# pureVCO.net
KiCad netlist of a schematic drawn in EAGLE
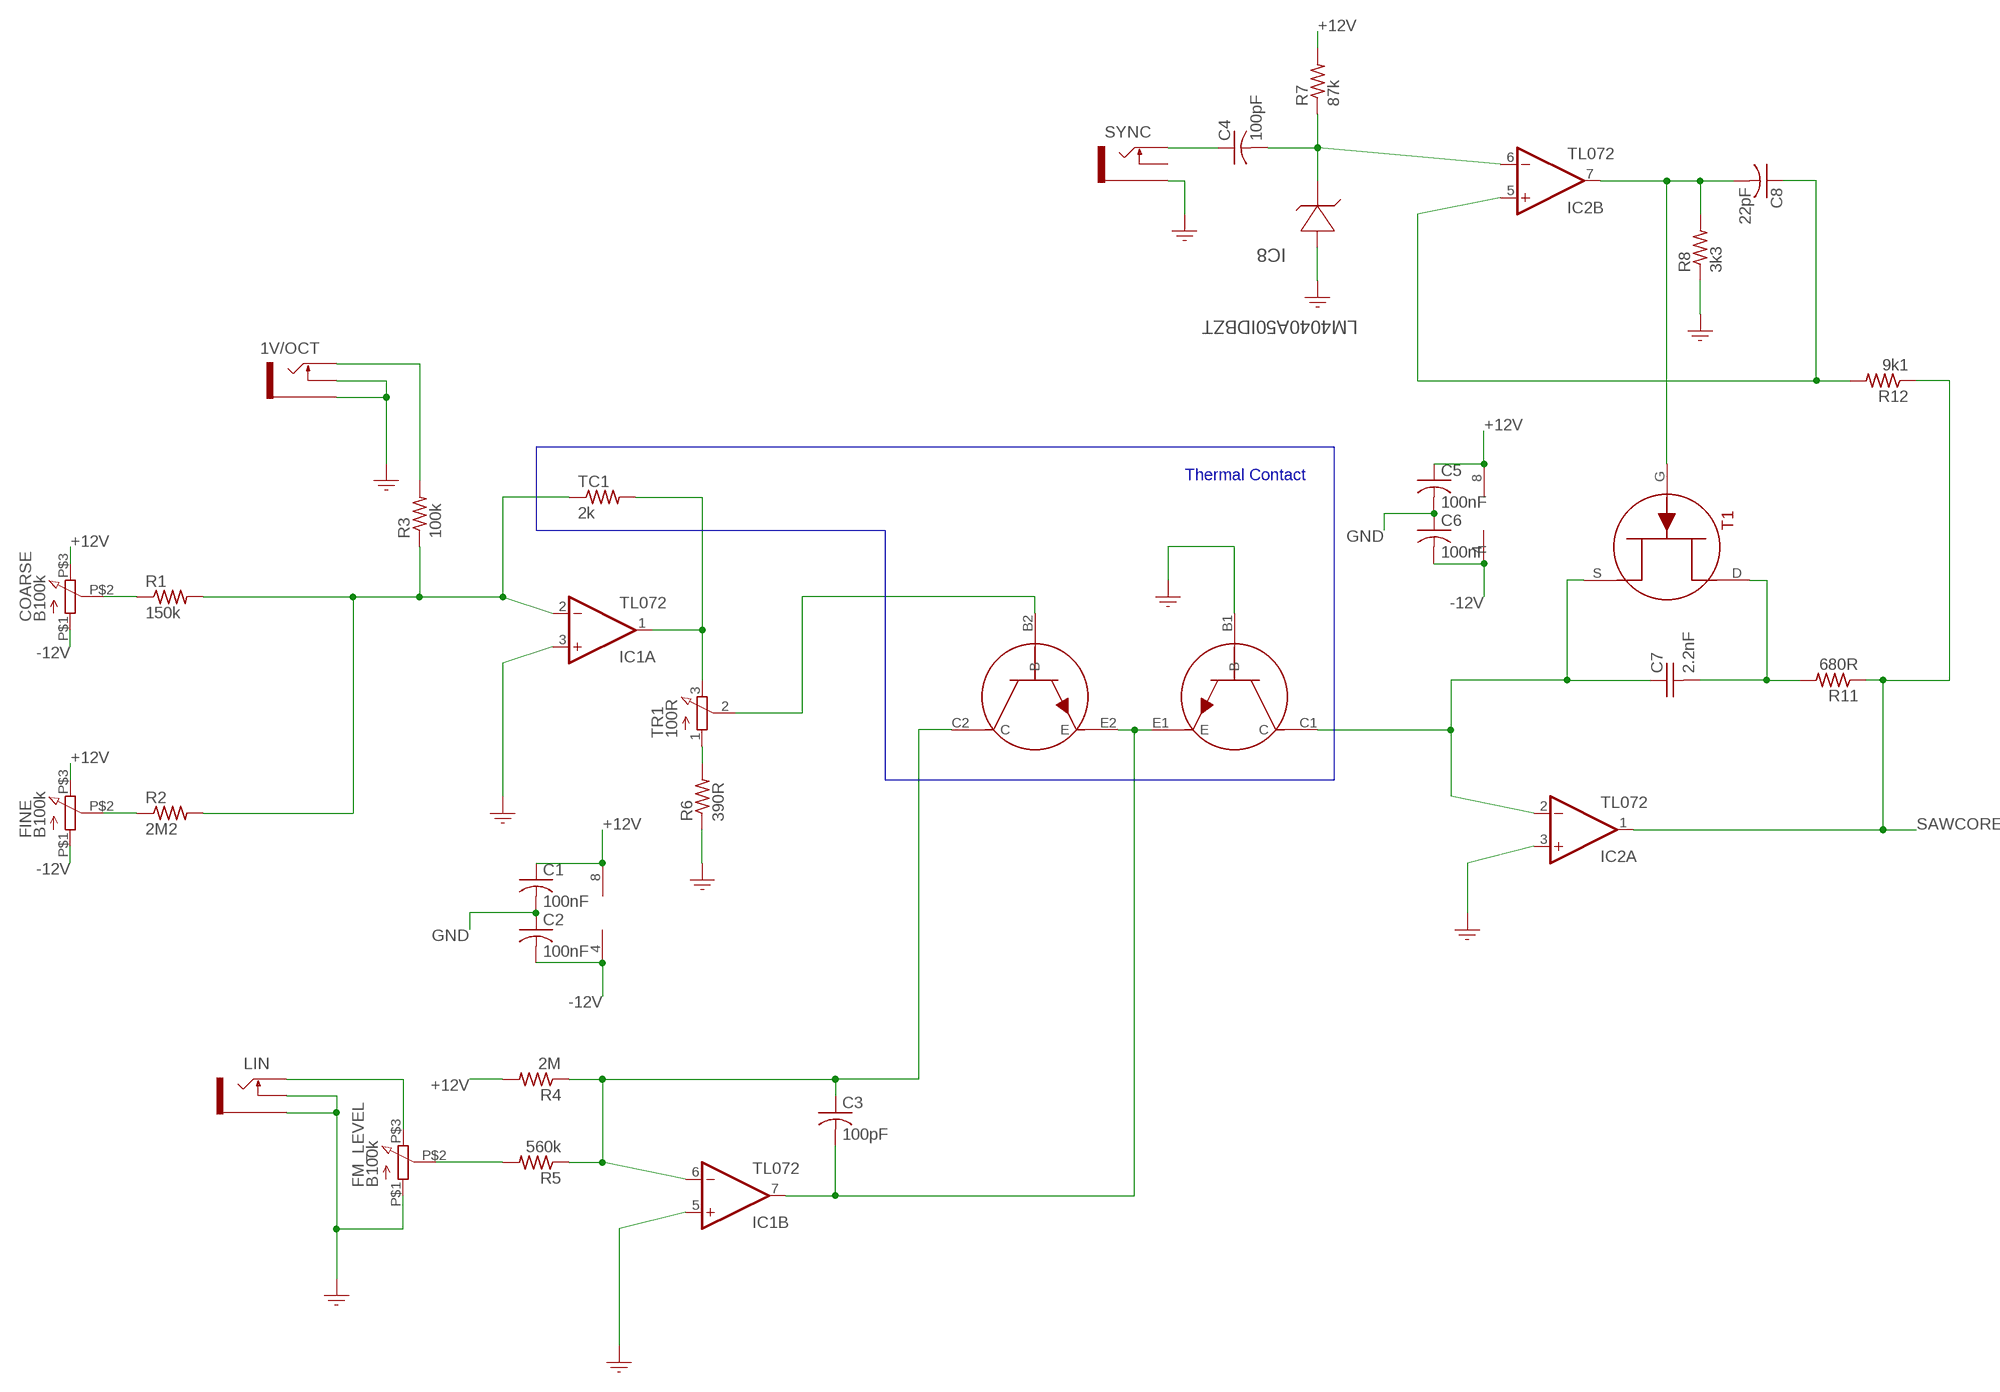
[diagram p0: schematic, sheet 1]
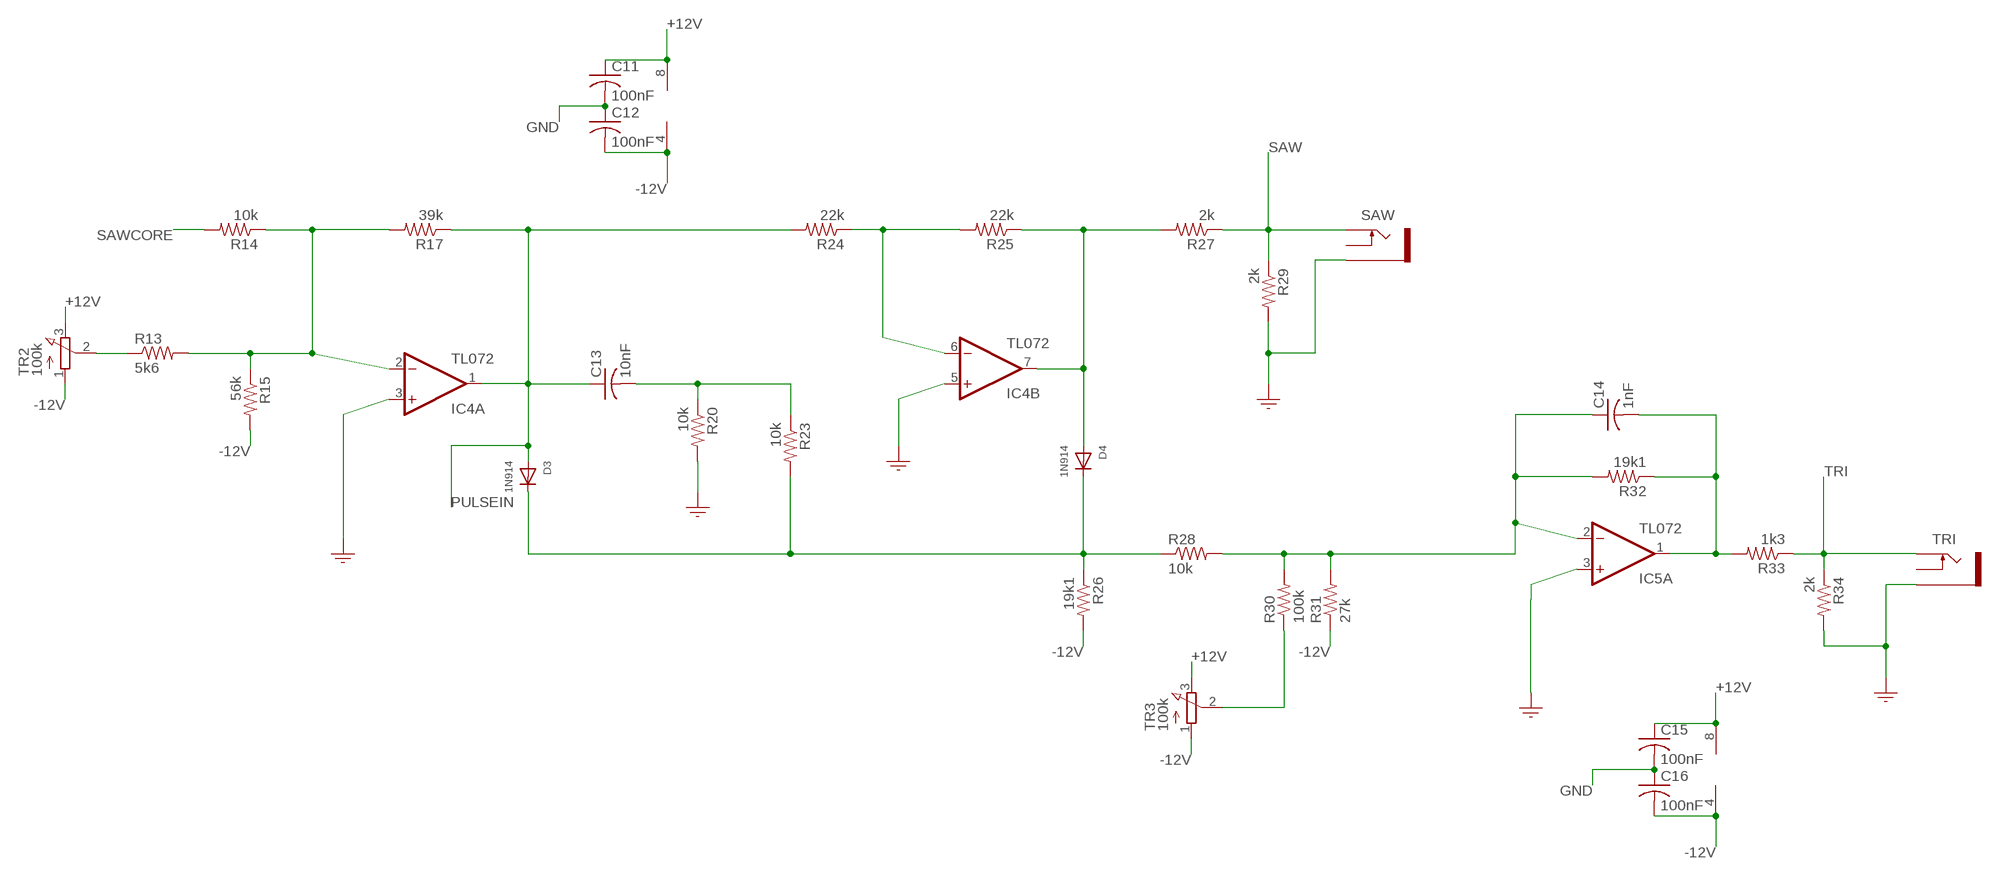
[diagram p1: schematic, sheet 2]
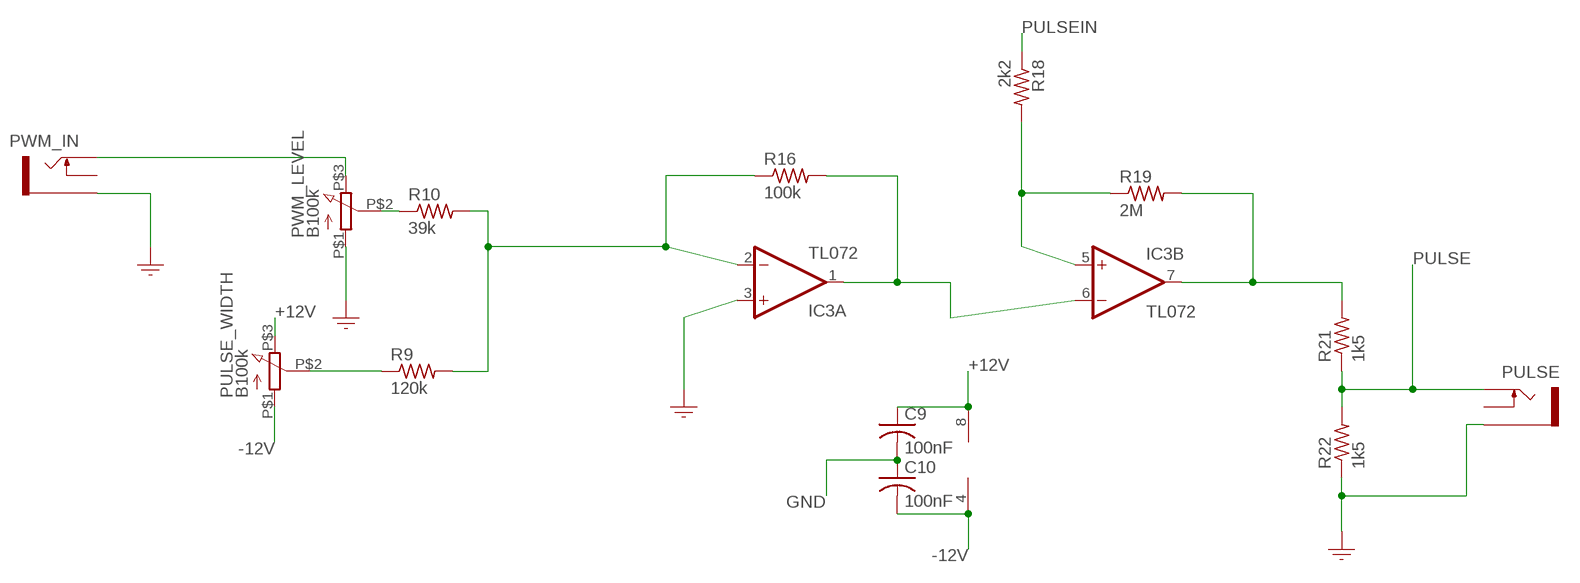
[diagram p2: schematic, sheet 3]
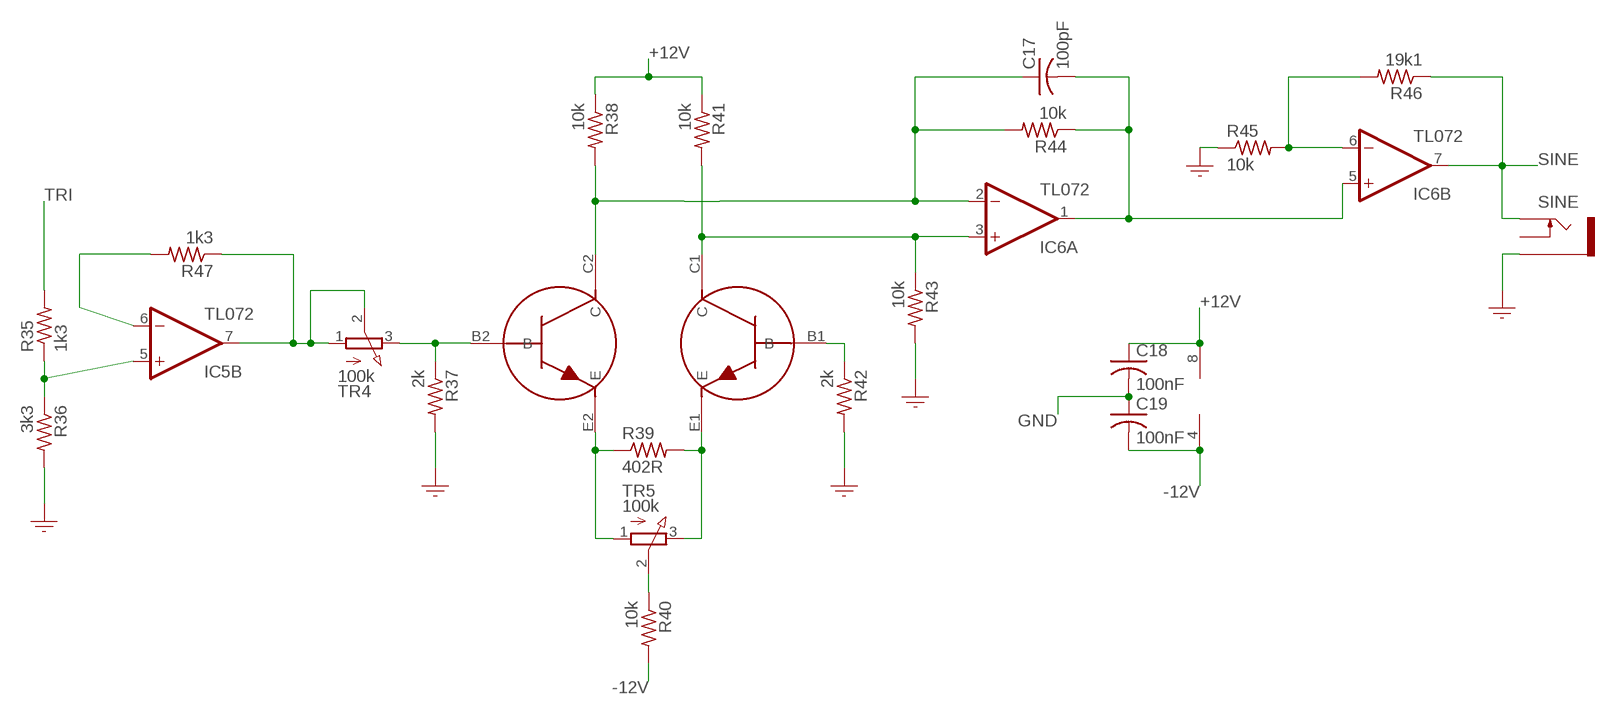
[diagram p3: schematic, sheet 4]
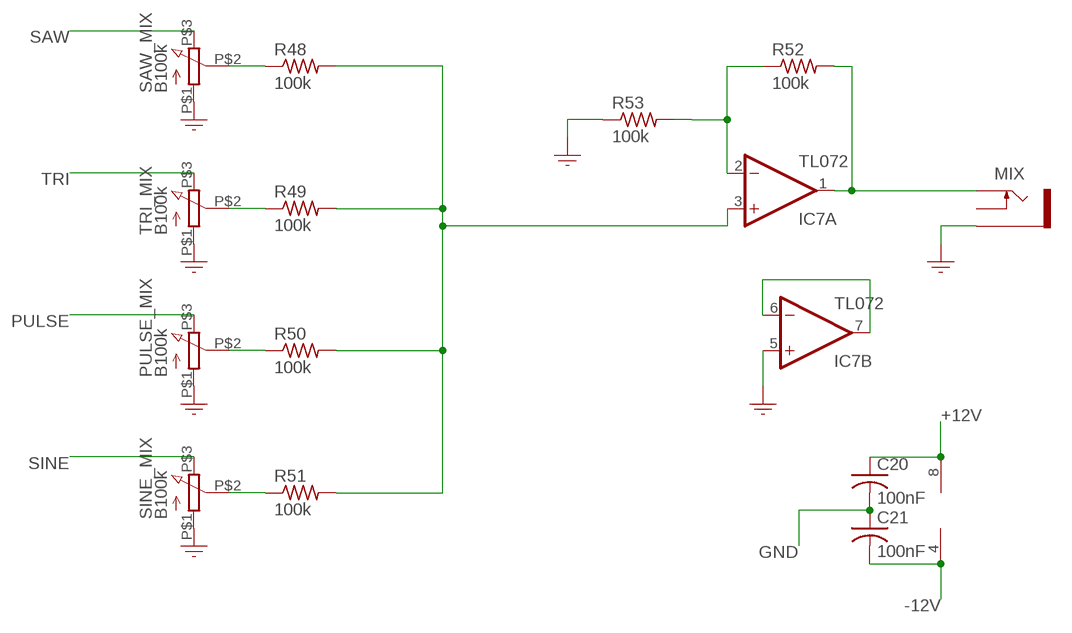
[diagram p4: schematic, sheet 5]
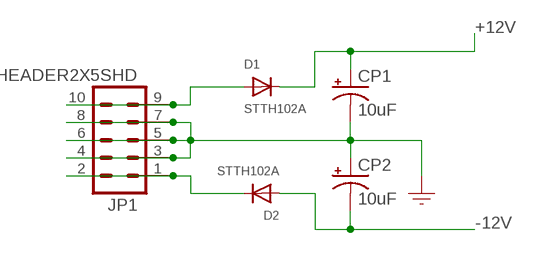
[diagram p5: schematic, sheet 6]

(export (version "E")
  (design (tool "Eeschema 10.0.6"))
  (components
    (comp (ref "1V/OCT")
      (value "PJ301M-12")
      (footprint "eagle-import:PJ301M-12")
      (libsource (lib "eagle-import") (part "SOCKET_MONO_3.5MMPJ301M-12"))
    )
    (comp (ref "C1")
      (value "100nF")
      (footprint "eagle-import:C0805")
      (libsource (lib "eagle-import") (part "CAPACITOR-USC0805"))
    )
    (comp (ref "C2")
      (value "100nF")
      (footprint "eagle-import:C0805")
      (libsource (lib "eagle-import") (part "CAPACITOR-USC0805"))
    )
    (comp (ref "C3")
      (value "100pF")
      (footprint "eagle-import:C0805")
      (libsource (lib "eagle-import") (part "CAPACITOR-USC0805"))
    )
    (comp (ref "C4")
      (value "100pF")
      (footprint "eagle-import:C0805")
      (libsource (lib "eagle-import") (part "CAPACITOR-USC0805"))
    )
    (comp (ref "C5")
      (value "100nF")
      (footprint "eagle-import:C0805")
      (libsource (lib "eagle-import") (part "CAPACITOR-USC0805"))
    )
    (comp (ref "C6")
      (value "100nF")
      (footprint "eagle-import:C0805")
      (libsource (lib "eagle-import") (part "CAPACITOR-USC0805"))
    )
    (comp (ref "C7")
      (value "2.2nF")
      (footprint "eagle-import:POLY_CAP")
      (libsource (lib "eagle-import") (part "CAPACITOR_POLYFILM"))
    )
    (comp (ref "C8")
      (value "22pF")
      (footprint "eagle-import:C0805")
      (libsource (lib "eagle-import") (part "CAPACITOR-USC0805"))
    )
    (comp (ref "COARSE")
      (value "B100k")
      (footprint "eagle-import:POTENTIOMETER_9MM")
      (libsource (lib "eagle-import") (part "RESISTOR_VARIABLE9MM_POT"))
    )
    (comp (ref "FINE")
      (value "B100k")
      (footprint "eagle-import:POTENTIOMETER_9MM")
      (libsource (lib "eagle-import") (part "RESISTOR_VARIABLE9MM_POT"))
    )
    (comp (ref "FM_LEVEL")
      (value "B100k")
      (footprint "eagle-import:POTENTIOMETER_9MM")
      (libsource (lib "eagle-import") (part "RESISTOR_VARIABLE9MM_POT"))
    )
    (comp (ref "IC1")
      (value "TL072")
      (footprint "eagle-import:SO08")
      (libsource (lib "eagle-import") (part "OPAMP_DUALD"))
    )
    (comp (ref "IC2")
      (value "TL072")
      (footprint "eagle-import:SO08")
      (libsource (lib "eagle-import") (part "OPAMP_DUALD"))
    )
    (comp (ref "IC8")
      (value "LM4040A50IDBZT")
      (footprint "eagle-import:SOT95P237X112-3N")
      (libsource (lib "eagle-import") (part "VOLTAGE_REF"))
    )
    (comp (ref "LIN")
      (value "PJ301M-12")
      (footprint "eagle-import:PJ301M-12")
      (libsource (lib "eagle-import") (part "SOCKET_MONO_3.5MMPJ301M-12"))
    )
    (comp (ref "R1")
      (value "150k")
      (footprint "eagle-import:R0805")
      (libsource (lib "eagle-import") (part "RESISTOR_USR0805"))
    )
    (comp (ref "R2")
      (value "2M2")
      (footprint "eagle-import:R0805")
      (libsource (lib "eagle-import") (part "RESISTOR_USR0805"))
    )
    (comp (ref "R3")
      (value "100k")
      (footprint "eagle-import:R0805")
      (libsource (lib "eagle-import") (part "RESISTOR_USR0805"))
    )
    (comp (ref "R4")
      (value "2M")
      (footprint "eagle-import:R0805")
      (libsource (lib "eagle-import") (part "RESISTOR_USR0805"))
    )
    (comp (ref "R5")
      (value "560k")
      (footprint "eagle-import:R0805")
      (libsource (lib "eagle-import") (part "RESISTOR_USR0805"))
    )
    (comp (ref "R6")
      (value "390R")
      (footprint "eagle-import:R0805")
      (libsource (lib "eagle-import") (part "RESISTOR_USR0805"))
    )
    (comp (ref "R7")
      (value "87k")
      (footprint "eagle-import:R0805")
      (libsource (lib "eagle-import") (part "RESISTOR_USR0805"))
    )
    (comp (ref "R8")
      (value "3k3")
      (footprint "eagle-import:R0805")
      (libsource (lib "eagle-import") (part "RESISTOR_USR0805"))
    )
    (comp (ref "R11")
      (value "680R")
      (footprint "eagle-import:R0805")
      (libsource (lib "eagle-import") (part "RESISTOR_USR0805"))
    )
    (comp (ref "R12")
      (value "9k1")
      (footprint "eagle-import:R0805")
      (libsource (lib "eagle-import") (part "RESISTOR_USR0805"))
    )
    (comp (ref "SYNC")
      (value "PJ301M-12")
      (footprint "eagle-import:PJ301M-12")
      (libsource (lib "eagle-import") (part "SOCKET_MONO_3.5MMPJ301M-12"))
    )
    (comp (ref "T1")
      (value "MMBFJ309")
      (footprint "eagle-import:N_CHN")
      (libsource (lib "eagle-import") (part "TRANSISTOR_JFET_N_CHN"))
    )
    (comp (ref "TC1")
      (value "2k")
      (footprint "eagle-import:0204_7")
      (libsource (lib "eagle-import") (part "RESISTOR_US0204/7"))
    )
    (comp (ref "TP1")
      (value "DMMT3904W-7-F")
      (footprint "eagle-import:TRANS_PAIR")
      (libsource (lib "eagle-import") (part "TRANSISTOR_PAIR_NPN"))
    )
    (comp (ref "TR1")
      (value "100R")
      (footprint "eagle-import:TRIMMER_TH")
      (libsource (lib "eagle-import") (part "RESISTOR_VARIABLETRIMMER_TH"))
    )
    (comp (ref "CP1")
      (value "10uF")
      (footprint "eagle-import:153CLV-0505")
      (libsource (lib "eagle-import") (part "CAPACITOR_POL-US153CLV-0505"))
    )
    (comp (ref "CP2")
      (value "10uF")
      (footprint "eagle-import:153CLV-0505")
      (libsource (lib "eagle-import") (part "CAPACITOR_POL-US153CLV-0505"))
    )
    (comp (ref "D1")
      (value "STTH102A")
      (footprint "eagle-import:SMADIODE")
      (libsource (lib "eagle-import") (part "DIODESMA"))
    )
    (comp (ref "D2")
      (value "STTH102A")
      (footprint "eagle-import:SMADIODE")
      (libsource (lib "eagle-import") (part "DIODESMA"))
    )
    (comp (ref "JP1")
      (value "HEADER2X5SHD")
      (footprint "eagle-import:2X5-SHROUDED")
      (libsource (lib "eagle-import") (part "HEADER2X5SHD"))
    )
    (comp (ref "C11")
      (value "100nF")
      (footprint "eagle-import:C0805")
      (libsource (lib "eagle-import") (part "CAPACITOR-USC0805"))
    )
    (comp (ref "C12")
      (value "100nF")
      (footprint "eagle-import:C0805")
      (libsource (lib "eagle-import") (part "CAPACITOR-USC0805"))
    )
    (comp (ref "C13")
      (value "10nF")
      (footprint "eagle-import:C0805")
      (libsource (lib "eagle-import") (part "CAPACITOR-USC0805"))
    )
    (comp (ref "C14")
      (value "1nF")
      (footprint "eagle-import:C0805")
      (libsource (lib "eagle-import") (part "CAPACITOR-USC0805"))
    )
    (comp (ref "C15")
      (value "100nF")
      (footprint "eagle-import:C0805")
      (libsource (lib "eagle-import") (part "CAPACITOR-USC0805"))
    )
    (comp (ref "C16")
      (value "100nF")
      (footprint "eagle-import:C0805")
      (libsource (lib "eagle-import") (part "CAPACITOR-USC0805"))
    )
    (comp (ref "D3")
      (value "1N914")
      (footprint "eagle-import:SOD-323F")
      (libsource (lib "eagle-import") (part "DIODESOD-323F"))
    )
    (comp (ref "D4")
      (value "1N914")
      (footprint "eagle-import:SOD-323F")
      (libsource (lib "eagle-import") (part "DIODESOD-323F"))
    )
    (comp (ref "IC4")
      (value "TL072")
      (footprint "eagle-import:SO08")
      (libsource (lib "eagle-import") (part "OPAMP_DUALD"))
    )
    (comp (ref "IC5")
      (value "TL072")
      (footprint "eagle-import:SO08")
      (libsource (lib "eagle-import") (part "OPAMP_DUALD"))
    )
    (comp (ref "R13")
      (value "5k6")
      (footprint "eagle-import:R0805")
      (libsource (lib "eagle-import") (part "RESISTOR_USR0805"))
    )
    (comp (ref "R14")
      (value "10k")
      (footprint "eagle-import:R0805")
      (libsource (lib "eagle-import") (part "RESISTOR_USR0805"))
    )
    (comp (ref "R15")
      (value "56k")
      (footprint "eagle-import:R0805")
      (libsource (lib "eagle-import") (part "RESISTOR_USR0805"))
    )
    (comp (ref "R17")
      (value "39k")
      (footprint "eagle-import:R0805")
      (libsource (lib "eagle-import") (part "RESISTOR_USR0805"))
    )
    (comp (ref "R20")
      (value "10k")
      (footprint "eagle-import:R0805")
      (libsource (lib "eagle-import") (part "RESISTOR_USR0805"))
    )
    (comp (ref "R23")
      (value "10k")
      (footprint "eagle-import:R0805")
      (libsource (lib "eagle-import") (part "RESISTOR_USR0805"))
    )
    (comp (ref "R24")
      (value "22k")
      (footprint "eagle-import:R0805")
      (libsource (lib "eagle-import") (part "RESISTOR_USR0805"))
    )
    (comp (ref "R25")
      (value "22k")
      (footprint "eagle-import:R0805")
      (libsource (lib "eagle-import") (part "RESISTOR_USR0805"))
    )
    (comp (ref "R26")
      (value "19k1")
      (footprint "eagle-import:R0805")
      (libsource (lib "eagle-import") (part "RESISTOR_USR0805"))
    )
    (comp (ref "R27")
      (value "2k")
      (footprint "eagle-import:R0805")
      (libsource (lib "eagle-import") (part "RESISTOR_USR0805"))
    )
    (comp (ref "R28")
      (value "10k")
      (footprint "eagle-import:R0805")
      (libsource (lib "eagle-import") (part "RESISTOR_USR0805"))
    )
    (comp (ref "R29")
      (value "2k")
      (footprint "eagle-import:R0805")
      (libsource (lib "eagle-import") (part "RESISTOR_USR0805"))
    )
    (comp (ref "R30")
      (value "100k")
      (footprint "eagle-import:R0805")
      (libsource (lib "eagle-import") (part "RESISTOR_USR0805"))
    )
    (comp (ref "R31")
      (value "27k")
      (footprint "eagle-import:R0805")
      (libsource (lib "eagle-import") (part "RESISTOR_USR0805"))
    )
    (comp (ref "R32")
      (value "19k1")
      (footprint "eagle-import:R0805")
      (libsource (lib "eagle-import") (part "RESISTOR_USR0805"))
    )
    (comp (ref "R33")
      (value "1k3")
      (footprint "eagle-import:R0805")
      (libsource (lib "eagle-import") (part "RESISTOR_USR0805"))
    )
    (comp (ref "R34")
      (value "2k")
      (footprint "eagle-import:R0805")
      (libsource (lib "eagle-import") (part "RESISTOR_USR0805"))
    )
    (comp (ref "SAW")
      (value "PJ301M-12")
      (footprint "eagle-import:PJ301M-12")
      (libsource (lib "eagle-import") (part "SOCKET_MONO_3.5MMPJ301M-12"))
    )
    (comp (ref "TR2")
      (value "100k")
      (footprint "eagle-import:TRIMMER_TH")
      (libsource (lib "eagle-import") (part "RESISTOR_VARIABLETRIMMER_TH"))
    )
    (comp (ref "TR3")
      (value "100k")
      (footprint "eagle-import:TRIMMER_TH")
      (libsource (lib "eagle-import") (part "RESISTOR_VARIABLETRIMMER_TH"))
    )
    (comp (ref "TRI")
      (value "PJ301M-12")
      (footprint "eagle-import:PJ301M-12")
      (libsource (lib "eagle-import") (part "SOCKET_MONO_3.5MMPJ301M-12"))
    )
    (comp (ref "C9")
      (value "100nF")
      (footprint "eagle-import:C0805")
      (libsource (lib "eagle-import") (part "CAPACITOR-USC0805"))
    )
    (comp (ref "C10")
      (value "100nF")
      (footprint "eagle-import:C0805")
      (libsource (lib "eagle-import") (part "CAPACITOR-USC0805"))
    )
    (comp (ref "IC3")
      (value "TL072")
      (footprint "eagle-import:SO08")
      (libsource (lib "eagle-import") (part "OPAMP_DUALD"))
    )
    (comp (ref "PULSE")
      (value "PJ301M-12")
      (footprint "eagle-import:PJ301M-12")
      (libsource (lib "eagle-import") (part "SOCKET_MONO_3.5MMPJ301M-12"))
    )
    (comp (ref "PULSE_WIDTH")
      (value "B100k")
      (footprint "eagle-import:POTENTIOMETER_9MM")
      (libsource (lib "eagle-import") (part "RESISTOR_VARIABLE9MM_POT"))
    )
    (comp (ref "PWM_IN")
      (value "PJ301M-12")
      (footprint "eagle-import:PJ301M-12")
      (libsource (lib "eagle-import") (part "SOCKET_MONO_3.5MMPJ301M-12"))
    )
    (comp (ref "PWM_LEVEL")
      (value "B100k")
      (footprint "eagle-import:POTENTIOMETER_9MM")
      (libsource (lib "eagle-import") (part "RESISTOR_VARIABLE9MM_POT"))
    )
    (comp (ref "R9")
      (value "120k")
      (footprint "eagle-import:R0805")
      (libsource (lib "eagle-import") (part "RESISTOR_USR0805"))
    )
    (comp (ref "R10")
      (value "39k")
      (footprint "eagle-import:R0805")
      (libsource (lib "eagle-import") (part "RESISTOR_USR0805"))
    )
    (comp (ref "R16")
      (value "100k")
      (footprint "eagle-import:R0805")
      (libsource (lib "eagle-import") (part "RESISTOR_USR0805"))
    )
    (comp (ref "R18")
      (value "2k2")
      (footprint "eagle-import:R0805")
      (libsource (lib "eagle-import") (part "RESISTOR_USR0805"))
    )
    (comp (ref "R19")
      (value "2M")
      (footprint "eagle-import:R0805")
      (libsource (lib "eagle-import") (part "RESISTOR_USR0805"))
    )
    (comp (ref "R21")
      (value "1k5")
      (footprint "eagle-import:R0805")
      (libsource (lib "eagle-import") (part "RESISTOR_USR0805"))
    )
    (comp (ref "R22")
      (value "1k5")
      (footprint "eagle-import:R0805")
      (libsource (lib "eagle-import") (part "RESISTOR_USR0805"))
    )
    (comp (ref "C17")
      (value "100pF")
      (footprint "eagle-import:C0805")
      (libsource (lib "eagle-import") (part "CAPACITOR-USC0805"))
    )
    (comp (ref "C18")
      (value "100nF")
      (footprint "eagle-import:C0805")
      (libsource (lib "eagle-import") (part "CAPACITOR-USC0805"))
    )
    (comp (ref "C19")
      (value "100nF")
      (footprint "eagle-import:C0805")
      (libsource (lib "eagle-import") (part "CAPACITOR-USC0805"))
    )
    (comp (ref "IC6")
      (value "TL072")
      (footprint "eagle-import:SO08")
      (libsource (lib "eagle-import") (part "OPAMP_DUALD"))
    )
    (comp (ref "R35")
      (value "1k3")
      (footprint "eagle-import:R0805")
      (libsource (lib "eagle-import") (part "RESISTOR_USR0805"))
    )
    (comp (ref "R36")
      (value "3k3")
      (footprint "eagle-import:R0805")
      (libsource (lib "eagle-import") (part "RESISTOR_USR0805"))
    )
    (comp (ref "R37")
      (value "2k")
      (footprint "eagle-import:R0805")
      (libsource (lib "eagle-import") (part "RESISTOR_USR0805"))
    )
    (comp (ref "R38")
      (value "10k")
      (footprint "eagle-import:R0805")
      (libsource (lib "eagle-import") (part "RESISTOR_USR0805"))
    )
    (comp (ref "R39")
      (value "402R")
      (footprint "eagle-import:R0805")
      (libsource (lib "eagle-import") (part "RESISTOR_USR0805"))
    )
    (comp (ref "R40")
      (value "10k")
      (footprint "eagle-import:R0805")
      (libsource (lib "eagle-import") (part "RESISTOR_USR0805"))
    )
    (comp (ref "R41")
      (value "10k")
      (footprint "eagle-import:R0805")
      (libsource (lib "eagle-import") (part "RESISTOR_USR0805"))
    )
    (comp (ref "R42")
      (value "2k")
      (footprint "eagle-import:R0805")
      (libsource (lib "eagle-import") (part "RESISTOR_USR0805"))
    )
    (comp (ref "R43")
      (value "10k")
      (footprint "eagle-import:R0805")
      (libsource (lib "eagle-import") (part "RESISTOR_USR0805"))
    )
    (comp (ref "R44")
      (value "10k")
      (footprint "eagle-import:R0805")
      (libsource (lib "eagle-import") (part "RESISTOR_USR0805"))
    )
    (comp (ref "R45")
      (value "10k")
      (footprint "eagle-import:R0805")
      (libsource (lib "eagle-import") (part "RESISTOR_USR0805"))
    )
    (comp (ref "R46")
      (value "19k1")
      (footprint "eagle-import:R0805")
      (libsource (lib "eagle-import") (part "RESISTOR_USR0805"))
    )
    (comp (ref "R47")
      (value "1k3")
      (footprint "eagle-import:R0805")
      (libsource (lib "eagle-import") (part "RESISTOR_USR0805"))
    )
    (comp (ref "SINE")
      (value "PJ301M-12")
      (footprint "eagle-import:PJ301M-12")
      (libsource (lib "eagle-import") (part "SOCKET_MONO_3.5MMPJ301M-12"))
    )
    (comp (ref "TP2")
      (value "DMMT3904W-7-F")
      (footprint "eagle-import:TRANS_PAIR")
      (libsource (lib "eagle-import") (part "TRANSISTOR_PAIR_NPN"))
    )
    (comp (ref "TR4")
      (value "100k")
      (footprint "eagle-import:TRIMMER_TH")
      (libsource (lib "eagle-import") (part "RESISTOR_VARIABLETRIMMER_TH"))
    )
    (comp (ref "TR5")
      (value "100k")
      (footprint "eagle-import:TRIMMER_TH")
      (libsource (lib "eagle-import") (part "RESISTOR_VARIABLETRIMMER_TH"))
    )
    (comp (ref "C20")
      (value "100nF")
      (footprint "eagle-import:C0805")
      (libsource (lib "eagle-import") (part "CAPACITOR-USC0805"))
    )
    (comp (ref "C21")
      (value "100nF")
      (footprint "eagle-import:C0805")
      (libsource (lib "eagle-import") (part "CAPACITOR-USC0805"))
    )
    (comp (ref "IC7")
      (value "TL072")
      (footprint "eagle-import:SO08")
      (libsource (lib "eagle-import") (part "OPAMP_DUALD"))
    )
    (comp (ref "MIX")
      (value "PJ301M-12")
      (footprint "eagle-import:PJ301M-12")
      (libsource (lib "eagle-import") (part "SOCKET_MONO_3.5MMPJ301M-12"))
    )
    (comp (ref "PULSE_MIX")
      (value "B100k")
      (footprint "eagle-import:POTENTIOMETER_9MM")
      (libsource (lib "eagle-import") (part "RESISTOR_VARIABLE9MM_POT"))
    )
    (comp (ref "R48")
      (value "100k")
      (footprint "eagle-import:R0805")
      (libsource (lib "eagle-import") (part "RESISTOR_USR0805"))
    )
    (comp (ref "R49")
      (value "100k")
      (footprint "eagle-import:R0805")
      (libsource (lib "eagle-import") (part "RESISTOR_USR0805"))
    )
    (comp (ref "R50")
      (value "100k")
      (footprint "eagle-import:R0805")
      (libsource (lib "eagle-import") (part "RESISTOR_USR0805"))
    )
    (comp (ref "R51")
      (value "100k")
      (footprint "eagle-import:R0805")
      (libsource (lib "eagle-import") (part "RESISTOR_USR0805"))
    )
    (comp (ref "R52")
      (value "100k")
      (footprint "eagle-import:R0805")
      (libsource (lib "eagle-import") (part "RESISTOR_USR0805"))
    )
    (comp (ref "R53")
      (value "100k")
      (footprint "eagle-import:R0805")
      (libsource (lib "eagle-import") (part "RESISTOR_USR0805"))
    )
    (comp (ref "SAW_MIX")
      (value "B100k")
      (footprint "eagle-import:POTENTIOMETER_9MM")
      (libsource (lib "eagle-import") (part "RESISTOR_VARIABLE9MM_POT"))
    )
    (comp (ref "SINE_MIX")
      (value "B100k")
      (footprint "eagle-import:POTENTIOMETER_9MM")
      (libsource (lib "eagle-import") (part "RESISTOR_VARIABLE9MM_POT"))
    )
    (comp (ref "TRI_MIX")
      (value "B100k")
      (footprint "eagle-import:POTENTIOMETER_9MM")
      (libsource (lib "eagle-import") (part "RESISTOR_VARIABLE9MM_POT"))
    )
  )
  (nets
    (net (code "1") (name "+12V") (class "Default")
      (node (ref "C1") (pin "1") (pinfunction "1_1") (pintype "passive"))
      (node (ref "C11") (pin "1") (pinfunction "1_1") (pintype "passive"))
      (node (ref "C15") (pin "1") (pinfunction "1_1") (pintype "passive"))
      (node (ref "C18") (pin "1") (pinfunction "1_1") (pintype "passive"))
      (node (ref "C20") (pin "1") (pinfunction "1_1") (pintype "passive"))
      (node (ref "C5") (pin "1") (pinfunction "1_1") (pintype "passive"))
      (node (ref "C9") (pin "1") (pinfunction "1_1") (pintype "passive"))
      (node (ref "COARSE") (pin "P$3") (pinfunction "3_P$3") (pintype "passive"))
      (node (ref "CP1") (pin "+") (pinfunction "+_+") (pintype "passive"))
      (node (ref "D1") (pin "C") (pinfunction "C_C") (pintype "passive"))
      (node (ref "FINE") (pin "P$3") (pinfunction "3_P$3") (pintype "passive"))
      (node (ref "IC1") (pin "8") (pinfunction "V+_8") (pintype "power_in"))
      (node (ref "IC2") (pin "8") (pinfunction "V+_8") (pintype "power_in"))
      (node (ref "IC3") (pin "8") (pinfunction "V+_8") (pintype "power_in"))
      (node (ref "IC4") (pin "8") (pinfunction "V+_8") (pintype "power_in"))
      (node (ref "IC5") (pin "8") (pinfunction "V+_8") (pintype "power_in"))
      (node (ref "IC6") (pin "8") (pinfunction "V+_8") (pintype "power_in"))
      (node (ref "IC7") (pin "8") (pinfunction "V+_8") (pintype "power_in"))
      (node (ref "PULSE_WIDTH") (pin "P$3") (pinfunction "3_P$3") (pintype "passive"))
      (node (ref "R38") (pin "1") (pinfunction "1_1") (pintype "passive"))
      (node (ref "R4") (pin "2") (pinfunction "2_2") (pintype "passive"))
      (node (ref "R41") (pin "1") (pinfunction "1_1") (pintype "passive"))
      (node (ref "R7") (pin "2") (pinfunction "2_2") (pintype "passive"))
      (node (ref "TR2") (pin "3") (pinfunction "3_3") (pintype "passive"))
      (node (ref "TR3") (pin "3") (pinfunction "3_3") (pintype "passive"))
    )
    (net (code "2") (name "-12V") (class "Default")
      (node (ref "C10") (pin "2") (pinfunction "2_2") (pintype "passive"))
      (node (ref "C12") (pin "2") (pinfunction "2_2") (pintype "passive"))
      (node (ref "C16") (pin "2") (pinfunction "2_2") (pintype "passive"))
      (node (ref "C19") (pin "2") (pinfunction "2_2") (pintype "passive"))
      (node (ref "C2") (pin "2") (pinfunction "2_2") (pintype "passive"))
      (node (ref "C21") (pin "2") (pinfunction "2_2") (pintype "passive"))
      (node (ref "C6") (pin "2") (pinfunction "2_2") (pintype "passive"))
      (node (ref "COARSE") (pin "P$1") (pinfunction "1_P$1") (pintype "passive"))
      (node (ref "CP2") (pin "-") (pinfunction "-_-") (pintype "passive"))
      (node (ref "D2") (pin "A") (pinfunction "A_A") (pintype "passive"))
      (node (ref "FINE") (pin "P$1") (pinfunction "1_P$1") (pintype "passive"))
      (node (ref "IC1") (pin "4") (pinfunction "V-_4") (pintype "power_in"))
      (node (ref "IC2") (pin "4") (pinfunction "V-_4") (pintype "power_in"))
      (node (ref "IC3") (pin "4") (pinfunction "V-_4") (pintype "power_in"))
      (node (ref "IC4") (pin "4") (pinfunction "V-_4") (pintype "power_in"))
      (node (ref "IC5") (pin "4") (pinfunction "V-_4") (pintype "power_in"))
      (node (ref "IC6") (pin "4") (pinfunction "V-_4") (pintype "power_in"))
      (node (ref "IC7") (pin "4") (pinfunction "V-_4") (pintype "power_in"))
      (node (ref "PULSE_WIDTH") (pin "P$1") (pinfunction "1_P$1") (pintype "passive"))
      (node (ref "R15") (pin "2") (pinfunction "2_2") (pintype "passive"))
      (node (ref "R26") (pin "2") (pinfunction "2_2") (pintype "passive"))
      (node (ref "R31") (pin "1") (pinfunction "1_1") (pintype "passive"))
      (node (ref "R40") (pin "2") (pinfunction "2_2") (pintype "passive"))
      (node (ref "TR2") (pin "1") (pinfunction "1_1") (pintype "passive"))
      (node (ref "TR3") (pin "1") (pinfunction "1_1") (pintype "passive"))
    )
    (net (code "3") (name "GND") (class "Default")
      (node (ref "1V/OCT") (pin "GND") (pinfunction "SLEEVE_GND") (pintype "passive"))
      (node (ref "1V/OCT") (pin "NORM") (pinfunction "SWITCH_NORM") (pintype "passive"))
      (node (ref "C1") (pin "2") (pinfunction "2_2") (pintype "passive"))
      (node (ref "C10") (pin "1") (pinfunction "1_1") (pintype "passive"))
      (node (ref "C11") (pin "2") (pinfunction "2_2") (pintype "passive"))
      (node (ref "C12") (pin "1") (pinfunction "1_1") (pintype "passive"))
      (node (ref "C15") (pin "2") (pinfunction "2_2") (pintype "passive"))
      (node (ref "C16") (pin "1") (pinfunction "1_1") (pintype "passive"))
      (node (ref "C18") (pin "2") (pinfunction "2_2") (pintype "passive"))
      (node (ref "C19") (pin "1") (pinfunction "1_1") (pintype "passive"))
      (node (ref "C2") (pin "1") (pinfunction "1_1") (pintype "passive"))
      (node (ref "C20") (pin "2") (pinfunction "2_2") (pintype "passive"))
      (node (ref "C21") (pin "1") (pinfunction "1_1") (pintype "passive"))
      (node (ref "C5") (pin "2") (pinfunction "2_2") (pintype "passive"))
      (node (ref "C6") (pin "1") (pinfunction "1_1") (pintype "passive"))
      (node (ref "C9") (pin "2") (pinfunction "2_2") (pintype "passive"))
      (node (ref "CP1") (pin "-") (pinfunction "-_-") (pintype "passive"))
      (node (ref "CP2") (pin "+") (pinfunction "+_+") (pintype "passive"))
      (node (ref "FM_LEVEL") (pin "P$1") (pinfunction "1_P$1") (pintype "passive"))
      (node (ref "IC1") (pin "3") (pinfunction "+IN_3") (pintype "input"))
      (node (ref "IC1") (pin "5") (pinfunction "+IN_5") (pintype "input"))
      (node (ref "IC2") (pin "3") (pinfunction "+IN_3") (pintype "input"))
      (node (ref "IC3") (pin "3") (pinfunction "+IN_3") (pintype "input"))
      (node (ref "IC4") (pin "3") (pinfunction "+IN_3") (pintype "input"))
      (node (ref "IC4") (pin "5") (pinfunction "+IN_5") (pintype "input"))
      (node (ref "IC5") (pin "3") (pinfunction "+IN_3") (pintype "input"))
      (node (ref "IC7") (pin "5") (pinfunction "+IN_5") (pintype "input"))
      (node (ref "IC8") (pin "2") (pinfunction "ANODE_2") (pintype "input"))
      (node (ref "JP1") (pin "3") (pinfunction "3_3") (pintype "passive"))
      (node (ref "JP1") (pin "4") (pinfunction "4_4") (pintype "passive"))
      (node (ref "JP1") (pin "5") (pinfunction "5_5") (pintype "passive"))
      (node (ref "JP1") (pin "6") (pinfunction "6_6") (pintype "passive"))
      (node (ref "JP1") (pin "7") (pinfunction "7_7") (pintype "passive"))
      (node (ref "JP1") (pin "8") (pinfunction "8_8") (pintype "passive"))
      (node (ref "LIN") (pin "GND") (pinfunction "SLEEVE_GND") (pintype "passive"))
      (node (ref "LIN") (pin "NORM") (pinfunction "SWITCH_NORM") (pintype "passive"))
      (node (ref "MIX") (pin "GND") (pinfunction "SLEEVE_GND") (pintype "passive"))
      (node (ref "PULSE") (pin "GND") (pinfunction "SLEEVE_GND") (pintype "passive"))
      (node (ref "PULSE_MIX") (pin "P$1") (pinfunction "1_P$1") (pintype "passive"))
      (node (ref "PWM_IN") (pin "GND") (pinfunction "SLEEVE_GND") (pintype "passive"))
      (node (ref "PWM_LEVEL") (pin "P$1") (pinfunction "1_P$1") (pintype "passive"))
      (node (ref "R20") (pin "2") (pinfunction "2_2") (pintype "passive"))
      (node (ref "R22") (pin "1") (pinfunction "1_1") (pintype "passive"))
      (node (ref "R29") (pin "2") (pinfunction "2_2") (pintype "passive"))
      (node (ref "R34") (pin "2") (pinfunction "2_2") (pintype "passive"))
      (node (ref "R36") (pin "2") (pinfunction "2_2") (pintype "passive"))
      (node (ref "R37") (pin "2") (pinfunction "2_2") (pintype "passive"))
      (node (ref "R42") (pin "2") (pinfunction "2_2") (pintype "passive"))
      (node (ref "R43") (pin "2") (pinfunction "2_2") (pintype "passive"))
      (node (ref "R45") (pin "1") (pinfunction "1_1") (pintype "passive"))
      (node (ref "R53") (pin "1") (pinfunction "1_1") (pintype "passive"))
      (node (ref "R6") (pin "1") (pinfunction "1_1") (pintype "passive"))
      (node (ref "R8") (pin "1") (pinfunction "1_1") (pintype "passive"))
      (node (ref "SAW") (pin "GND") (pinfunction "SLEEVE_GND") (pintype "passive"))
      (node (ref "SAW_MIX") (pin "P$1") (pinfunction "1_P$1") (pintype "passive"))
      (node (ref "SINE") (pin "GND") (pinfunction "SLEEVE_GND") (pintype "passive"))
      (node (ref "SINE_MIX") (pin "P$1") (pinfunction "1_P$1") (pintype "passive"))
      (node (ref "SYNC") (pin "GND") (pinfunction "SLEEVE_GND") (pintype "passive"))
      (node (ref "TP1") (pin "B1") (pinfunction "B_B1") (pintype "bidirectional"))
      (node (ref "TRI") (pin "GND") (pinfunction "SLEEVE_GND") (pintype "passive"))
      (node (ref "TRI_MIX") (pin "P$1") (pinfunction "1_P$1") (pintype "passive"))
    )
    (net (code "4") (name "Net-(1V/OCT-PadTIP)") (class "Default")
      (node (ref "1V/OCT") (pin "TIP") (pinfunction "TIP_TIP") (pintype "passive"))
      (node (ref "R3") (pin "2") (pinfunction "2_2") (pintype "passive"))
    )
    (net (code "5") (name "Net-(C4-Pad1)") (class "Default")
      (node (ref "C4") (pin "1") (pinfunction "1_1") (pintype "passive"))
      (node (ref "SYNC") (pin "TIP") (pinfunction "TIP_TIP") (pintype "passive"))
    )
    (net (code "6") (name "Net-(C7-+)") (class "Default")
      (node (ref "C7") (pin "1") (pinfunction "+_1") (pintype "passive"))
      (node (ref "IC2") (pin "2") (pinfunction "-IN_2") (pintype "input"))
      (node (ref "T1") (pin "S") (pinfunction "S_S") (pintype "bidirectional"))
      (node (ref "TP1") (pin "C1") (pinfunction "C_C1") (pintype "bidirectional"))
    )
    (net (code "7") (name "Net-(C7--)") (class "Default")
      (node (ref "C7") (pin "2") (pinfunction "-_2") (pintype "passive"))
      (node (ref "R11") (pin "2") (pinfunction "2_2") (pintype "passive"))
      (node (ref "T1") (pin "D") (pinfunction "D_D") (pintype "bidirectional"))
    )
    (net (code "8") (name "Net-(C13-Pad2)") (class "Default")
      (node (ref "C13") (pin "2") (pinfunction "2_2") (pintype "passive"))
      (node (ref "R20") (pin "1") (pinfunction "1_1") (pintype "passive"))
      (node (ref "R23") (pin "1") (pinfunction "1_1") (pintype "passive"))
    )
    (net (code "9") (name "Net-(COARSE-2)") (class "Default")
      (node (ref "COARSE") (pin "P$2") (pinfunction "2_P$2") (pintype "passive"))
      (node (ref "R1") (pin "1") (pinfunction "1_1") (pintype "passive"))
    )
    (net (code "10") (name "Net-(D1-PadA)") (class "Default")
      (node (ref "D1") (pin "A") (pinfunction "A_A") (pintype "passive"))
      (node (ref "JP1") (pin "10") (pinfunction "10_10") (pintype "passive"))
      (node (ref "JP1") (pin "9") (pinfunction "9_9") (pintype "passive"))
    )
    (net (code "11") (name "Net-(D2-PadC)") (class "Default")
      (node (ref "D2") (pin "C") (pinfunction "C_C") (pintype "passive"))
      (node (ref "JP1") (pin "1") (pinfunction "1_1") (pintype "passive"))
      (node (ref "JP1") (pin "2") (pinfunction "2_2") (pintype "passive"))
    )
    (net (code "12") (name "Net-(D3-PadC)") (class "Default")
      (node (ref "D3") (pin "C") (pinfunction "C_C") (pintype "passive"))
      (node (ref "D4") (pin "C") (pinfunction "C_C") (pintype "passive"))
      (node (ref "R23") (pin "2") (pinfunction "2_2") (pintype "passive"))
      (node (ref "R26") (pin "1") (pinfunction "1_1") (pintype "passive"))
      (node (ref "R28") (pin "1") (pinfunction "1_1") (pintype "passive"))
    )
    (net (code "13") (name "Net-(FINE-2)") (class "Default")
      (node (ref "FINE") (pin "P$2") (pinfunction "2_P$2") (pintype "passive"))
      (node (ref "R2") (pin "1") (pinfunction "1_1") (pintype "passive"))
    )
    (net (code "14") (name "Net-(FM_LEVEL-2)") (class "Default")
      (node (ref "FM_LEVEL") (pin "P$2") (pinfunction "2_P$2") (pintype "passive"))
      (node (ref "R5") (pin "2") (pinfunction "2_2") (pintype "passive"))
    )
    (net (code "15") (name "Net-(FM_LEVEL-3)") (class "Default")
      (node (ref "FM_LEVEL") (pin "P$3") (pinfunction "3_P$3") (pintype "passive"))
      (node (ref "LIN") (pin "TIP") (pinfunction "TIP_TIP") (pintype "passive"))
    )
    (net (code "16") (name "Net-(IC1A--IN)") (class "Default")
      (node (ref "IC1") (pin "2") (pinfunction "-IN_2") (pintype "input"))
      (node (ref "R1") (pin "2") (pinfunction "2_2") (pintype "passive"))
      (node (ref "R2") (pin "2") (pinfunction "2_2") (pintype "passive"))
      (node (ref "R3") (pin "1") (pinfunction "1_1") (pintype "passive"))
      (node (ref "TC1") (pin "1") (pinfunction "1_1") (pintype "passive"))
    )
    (net (code "17") (name "Net-(IC1A-OUT)") (class "Default")
      (node (ref "IC1") (pin "1") (pinfunction "OUT_1") (pintype "output"))
      (node (ref "TC1") (pin "2") (pinfunction "2_2") (pintype "passive"))
      (node (ref "TR1") (pin "3") (pinfunction "3_3") (pintype "passive"))
    )
    (net (code "18") (name "Net-(IC1B--IN)") (class "Default")
      (node (ref "C3") (pin "1") (pinfunction "1_1") (pintype "passive"))
      (node (ref "IC1") (pin "6") (pinfunction "-IN_6") (pintype "input"))
      (node (ref "R4") (pin "1") (pinfunction "1_1") (pintype "passive"))
      (node (ref "R5") (pin "1") (pinfunction "1_1") (pintype "passive"))
      (node (ref "TP1") (pin "C2") (pinfunction "C_C2") (pintype "bidirectional"))
    )
    (net (code "19") (name "Net-(IC1B-OUT)") (class "Default")
      (node (ref "C3") (pin "2") (pinfunction "2_2") (pintype "passive"))
      (node (ref "IC1") (pin "7") (pinfunction "OUT_7") (pintype "output"))
      (node (ref "TP1") (pin "E1") (pinfunction "E_E1") (pintype "bidirectional"))
      (node (ref "TP1") (pin "E2") (pinfunction "E_E2") (pintype "bidirectional"))
    )
    (net (code "20") (name "Net-(IC2B-+IN)") (class "Default")
      (node (ref "C8") (pin "1") (pinfunction "1_1") (pintype "passive"))
      (node (ref "IC2") (pin "5") (pinfunction "+IN_5") (pintype "input"))
      (node (ref "R12") (pin "2") (pinfunction "2_2") (pintype "passive"))
    )
    (net (code "21") (name "Net-(IC2B--IN)") (class "Default")
      (node (ref "C4") (pin "2") (pinfunction "2_2") (pintype "passive"))
      (node (ref "IC2") (pin "6") (pinfunction "-IN_6") (pintype "input"))
      (node (ref "IC8") (pin "1") (pinfunction "CATHODE_1") (pintype "output"))
      (node (ref "R7") (pin "1") (pinfunction "1_1") (pintype "passive"))
    )
    (net (code "22") (name "Net-(IC2B-OUT)") (class "Default")
      (node (ref "C8") (pin "2") (pinfunction "2_2") (pintype "passive"))
      (node (ref "IC2") (pin "7") (pinfunction "OUT_7") (pintype "output"))
      (node (ref "R8") (pin "2") (pinfunction "2_2") (pintype "passive"))
      (node (ref "T1") (pin "G") (pinfunction "G_G") (pintype "bidirectional"))
    )
    (net (code "23") (name "Net-(IC3A--IN)") (class "Default")
      (node (ref "IC3") (pin "2") (pinfunction "-IN_2") (pintype "input"))
      (node (ref "R10") (pin "2") (pinfunction "2_2") (pintype "passive"))
      (node (ref "R16") (pin "1") (pinfunction "1_1") (pintype "passive"))
      (node (ref "R9") (pin "2") (pinfunction "2_2") (pintype "passive"))
    )
    (net (code "24") (name "Net-(IC3A-OUT)") (class "Default")
      (node (ref "IC3") (pin "1") (pinfunction "OUT_1") (pintype "output"))
      (node (ref "IC3") (pin "6") (pinfunction "-IN_6") (pintype "input"))
      (node (ref "R16") (pin "2") (pinfunction "2_2") (pintype "passive"))
    )
    (net (code "25") (name "Net-(IC3B-+IN)") (class "Default")
      (node (ref "IC3") (pin "5") (pinfunction "+IN_5") (pintype "input"))
      (node (ref "R18") (pin "2") (pinfunction "2_2") (pintype "passive"))
      (node (ref "R19") (pin "1") (pinfunction "1_1") (pintype "passive"))
    )
    (net (code "26") (name "Net-(IC3B-OUT)") (class "Default")
      (node (ref "IC3") (pin "7") (pinfunction "OUT_7") (pintype "output"))
      (node (ref "R19") (pin "2") (pinfunction "2_2") (pintype "passive"))
      (node (ref "R21") (pin "2") (pinfunction "2_2") (pintype "passive"))
    )
    (net (code "27") (name "Net-(IC4A--IN)") (class "Default")
      (node (ref "IC4") (pin "2") (pinfunction "-IN_2") (pintype "input"))
      (node (ref "R13") (pin "2") (pinfunction "2_2") (pintype "passive"))
      (node (ref "R14") (pin "1") (pinfunction "1_1") (pintype "passive"))
      (node (ref "R15") (pin "1") (pinfunction "1_1") (pintype "passive"))
      (node (ref "R17") (pin "2") (pinfunction "2_2") (pintype "passive"))
    )
    (net (code "28") (name "Net-(IC4B--IN)") (class "Default")
      (node (ref "IC4") (pin "6") (pinfunction "-IN_6") (pintype "input"))
      (node (ref "R24") (pin "1") (pinfunction "1_1") (pintype "passive"))
      (node (ref "R25") (pin "2") (pinfunction "2_2") (pintype "passive"))
    )
    (net (code "29") (name "Net-(IC4B-OUT)") (class "Default")
      (node (ref "D4") (pin "A") (pinfunction "A_A") (pintype "passive"))
      (node (ref "IC4") (pin "7") (pinfunction "OUT_7") (pintype "output"))
      (node (ref "R25") (pin "1") (pinfunction "1_1") (pintype "passive"))
      (node (ref "R27") (pin "2") (pinfunction "2_2") (pintype "passive"))
    )
    (net (code "30") (name "Net-(IC5A--IN)") (class "Default")
      (node (ref "C14") (pin "1") (pinfunction "1_1") (pintype "passive"))
      (node (ref "IC5") (pin "2") (pinfunction "-IN_2") (pintype "input"))
      (node (ref "R28") (pin "2") (pinfunction "2_2") (pintype "passive"))
      (node (ref "R30") (pin "2") (pinfunction "2_2") (pintype "passive"))
      (node (ref "R31") (pin "2") (pinfunction "2_2") (pintype "passive"))
      (node (ref "R32") (pin "2") (pinfunction "2_2") (pintype "passive"))
    )
    (net (code "31") (name "Net-(IC5A-OUT)") (class "Default")
      (node (ref "C14") (pin "2") (pinfunction "2_2") (pintype "passive"))
      (node (ref "IC5") (pin "1") (pinfunction "OUT_1") (pintype "output"))
      (node (ref "R32") (pin "1") (pinfunction "1_1") (pintype "passive"))
      (node (ref "R33") (pin "2") (pinfunction "2_2") (pintype "passive"))
    )
    (net (code "32") (name "Net-(IC5B-+IN)") (class "Default")
      (node (ref "IC5") (pin "5") (pinfunction "+IN_5") (pintype "input"))
      (node (ref "R35") (pin "1") (pinfunction "1_1") (pintype "passive"))
      (node (ref "R36") (pin "1") (pinfunction "1_1") (pintype "passive"))
    )
    (net (code "33") (name "Net-(IC5B--IN)") (class "Default")
      (node (ref "IC5") (pin "6") (pinfunction "-IN_6") (pintype "input"))
      (node (ref "R47") (pin "2") (pinfunction "2_2") (pintype "passive"))
    )
    (net (code "34") (name "Net-(IC5B-OUT)") (class "Default")
      (node (ref "IC5") (pin "7") (pinfunction "OUT_7") (pintype "output"))
      (node (ref "R47") (pin "1") (pinfunction "1_1") (pintype "passive"))
      (node (ref "TR4") (pin "1") (pinfunction "1_1") (pintype "passive"))
      (node (ref "TR4") (pin "2") (pinfunction "2_2") (pintype "passive"))
    )
    (net (code "35") (name "Net-(IC6A-+IN)") (class "Default")
      (node (ref "IC6") (pin "3") (pinfunction "+IN_3") (pintype "input"))
      (node (ref "R41") (pin "2") (pinfunction "2_2") (pintype "passive"))
      (node (ref "R43") (pin "1") (pinfunction "1_1") (pintype "passive"))
      (node (ref "TP2") (pin "C1") (pinfunction "C_C1") (pintype "bidirectional"))
    )
    (net (code "36") (name "Net-(IC6A--IN)") (class "Default")
      (node (ref "C17") (pin "1") (pinfunction "1_1") (pintype "passive"))
      (node (ref "IC6") (pin "2") (pinfunction "-IN_2") (pintype "input"))
      (node (ref "R38") (pin "2") (pinfunction "2_2") (pintype "passive"))
      (node (ref "R44") (pin "2") (pinfunction "2_2") (pintype "passive"))
      (node (ref "TP2") (pin "C2") (pinfunction "C_C2") (pintype "bidirectional"))
    )
    (net (code "37") (name "Net-(IC6A-OUT)") (class "Default")
      (node (ref "C17") (pin "2") (pinfunction "2_2") (pintype "passive"))
      (node (ref "IC6") (pin "1") (pinfunction "OUT_1") (pintype "output"))
      (node (ref "IC6") (pin "5") (pinfunction "+IN_5") (pintype "input"))
      (node (ref "R44") (pin "1") (pinfunction "1_1") (pintype "passive"))
    )
    (net (code "38") (name "Net-(IC6B--IN)") (class "Default")
      (node (ref "IC6") (pin "6") (pinfunction "-IN_6") (pintype "input"))
      (node (ref "R45") (pin "2") (pinfunction "2_2") (pintype "passive"))
      (node (ref "R46") (pin "2") (pinfunction "2_2") (pintype "passive"))
    )
    (net (code "39") (name "Net-(IC7A-+IN)") (class "Default")
      (node (ref "IC7") (pin "3") (pinfunction "+IN_3") (pintype "input"))
      (node (ref "R48") (pin "2") (pinfunction "2_2") (pintype "passive"))
      (node (ref "R49") (pin "2") (pinfunction "2_2") (pintype "passive"))
      (node (ref "R50") (pin "2") (pinfunction "2_2") (pintype "passive"))
      (node (ref "R51") (pin "2") (pinfunction "2_2") (pintype "passive"))
    )
    (net (code "40") (name "Net-(IC7A--IN)") (class "Default")
      (node (ref "IC7") (pin "2") (pinfunction "-IN_2") (pintype "input"))
      (node (ref "R52") (pin "1") (pinfunction "1_1") (pintype "passive"))
      (node (ref "R53") (pin "2") (pinfunction "2_2") (pintype "passive"))
    )
    (net (code "41") (name "Net-(IC7A-OUT)") (class "Default")
      (node (ref "IC7") (pin "1") (pinfunction "OUT_1") (pintype "output"))
      (node (ref "MIX") (pin "TIP") (pinfunction "TIP_TIP") (pintype "passive"))
      (node (ref "R52") (pin "2") (pinfunction "2_2") (pintype "passive"))
    )
    (net (code "42") (name "Net-(IC7B--IN)") (class "Default")
      (node (ref "IC7") (pin "6") (pinfunction "-IN_6") (pintype "input"))
      (node (ref "IC7") (pin "7") (pinfunction "OUT_7") (pintype "output"))
    )
    (net (code "43") (name "Net-(PULSE_MIX-2)") (class "Default")
      (node (ref "PULSE_MIX") (pin "P$2") (pinfunction "2_P$2") (pintype "passive"))
      (node (ref "R50") (pin "1") (pinfunction "1_1") (pintype "passive"))
    )
    (net (code "44") (name "Net-(PULSE_WIDTH-2)") (class "Default")
      (node (ref "PULSE_WIDTH") (pin "P$2") (pinfunction "2_P$2") (pintype "passive"))
      (node (ref "R9") (pin "1") (pinfunction "1_1") (pintype "passive"))
    )
    (net (code "45") (name "Net-(PWM_LEVEL-2)") (class "Default")
      (node (ref "PWM_LEVEL") (pin "P$2") (pinfunction "2_P$2") (pintype "passive"))
      (node (ref "R10") (pin "1") (pinfunction "1_1") (pintype "passive"))
    )
    (net (code "46") (name "Net-(PWM_LEVEL-3)") (class "Default")
      (node (ref "PWM_IN") (pin "TIP") (pinfunction "TIP_TIP") (pintype "passive"))
      (node (ref "PWM_LEVEL") (pin "P$3") (pinfunction "3_P$3") (pintype "passive"))
    )
    (net (code "47") (name "Net-(R6-Pad2)") (class "Default")
      (node (ref "R6") (pin "2") (pinfunction "2_2") (pintype "passive"))
      (node (ref "TR1") (pin "1") (pinfunction "1_1") (pintype "passive"))
    )
    (net (code "48") (name "Net-(R13-Pad1)") (class "Default")
      (node (ref "R13") (pin "1") (pinfunction "1_1") (pintype "passive"))
      (node (ref "TR2") (pin "2") (pinfunction "2_2") (pintype "passive"))
    )
    (net (code "49") (name "Net-(R30-Pad1)") (class "Default")
      (node (ref "R30") (pin "1") (pinfunction "1_1") (pintype "passive"))
      (node (ref "TR3") (pin "2") (pinfunction "2_2") (pintype "passive"))
    )
    (net (code "50") (name "Net-(R40-Pad1)") (class "Default")
      (node (ref "R40") (pin "1") (pinfunction "1_1") (pintype "passive"))
      (node (ref "TR5") (pin "2") (pinfunction "2_2") (pintype "passive"))
    )
    (net (code "51") (name "Net-(SAW_MIX-2)") (class "Default")
      (node (ref "R48") (pin "1") (pinfunction "1_1") (pintype "passive"))
      (node (ref "SAW_MIX") (pin "P$2") (pinfunction "2_P$2") (pintype "passive"))
    )
    (net (code "52") (name "Net-(SINE_MIX-2)") (class "Default")
      (node (ref "R51") (pin "1") (pinfunction "1_1") (pintype "passive"))
      (node (ref "SINE_MIX") (pin "P$2") (pinfunction "2_P$2") (pintype "passive"))
    )
    (net (code "53") (name "Net-(TP1B-B)") (class "Default")
      (node (ref "TP1") (pin "B2") (pinfunction "B_B2") (pintype "bidirectional"))
      (node (ref "TR1") (pin "2") (pinfunction "2_2") (pintype "passive"))
    )
    (net (code "54") (name "Net-(TP2A-B)") (class "Default")
      (node (ref "R42") (pin "1") (pinfunction "1_1") (pintype "passive"))
      (node (ref "TP2") (pin "B1") (pinfunction "B_B1") (pintype "bidirectional"))
    )
    (net (code "55") (name "Net-(TP2A-E)") (class "Default")
      (node (ref "R39") (pin "2") (pinfunction "2_2") (pintype "passive"))
      (node (ref "TP2") (pin "E1") (pinfunction "E_E1") (pintype "bidirectional"))
      (node (ref "TR5") (pin "3") (pinfunction "3_3") (pintype "passive"))
    )
    (net (code "56") (name "Net-(TP2B-B)") (class "Default")
      (node (ref "R37") (pin "1") (pinfunction "1_1") (pintype "passive"))
      (node (ref "TP2") (pin "B2") (pinfunction "B_B2") (pintype "bidirectional"))
      (node (ref "TR4") (pin "3") (pinfunction "3_3") (pintype "passive"))
    )
    (net (code "57") (name "Net-(TP2B-E)") (class "Default")
      (node (ref "R39") (pin "1") (pinfunction "1_1") (pintype "passive"))
      (node (ref "TP2") (pin "E2") (pinfunction "E_E2") (pintype "bidirectional"))
      (node (ref "TR5") (pin "1") (pinfunction "1_1") (pintype "passive"))
    )
    (net (code "58") (name "Net-(TRI_MIX-2)") (class "Default")
      (node (ref "R49") (pin "1") (pinfunction "1_1") (pintype "passive"))
      (node (ref "TRI_MIX") (pin "P$2") (pinfunction "2_P$2") (pintype "passive"))
    )
    (net (code "59") (name "PULSE") (class "Default")
      (node (ref "PULSE") (pin "TIP") (pinfunction "TIP_TIP") (pintype "passive"))
      (node (ref "PULSE_MIX") (pin "P$3") (pinfunction "3_P$3") (pintype "passive"))
      (node (ref "R21") (pin "1") (pinfunction "1_1") (pintype "passive"))
      (node (ref "R22") (pin "2") (pinfunction "2_2") (pintype "passive"))
    )
    (net (code "60") (name "PULSEIN") (class "Default")
      (node (ref "C13") (pin "1") (pinfunction "1_1") (pintype "passive"))
      (node (ref "D3") (pin "A") (pinfunction "A_A") (pintype "passive"))
      (node (ref "IC4") (pin "1") (pinfunction "OUT_1") (pintype "output"))
      (node (ref "R17") (pin "1") (pinfunction "1_1") (pintype "passive"))
      (node (ref "R18") (pin "1") (pinfunction "1_1") (pintype "passive"))
      (node (ref "R24") (pin "2") (pinfunction "2_2") (pintype "passive"))
    )
    (net (code "61") (name "SAW") (class "Default")
      (node (ref "R27") (pin "1") (pinfunction "1_1") (pintype "passive"))
      (node (ref "R29") (pin "1") (pinfunction "1_1") (pintype "passive"))
      (node (ref "SAW") (pin "TIP") (pinfunction "TIP_TIP") (pintype "passive"))
      (node (ref "SAW_MIX") (pin "P$3") (pinfunction "3_P$3") (pintype "passive"))
    )
    (net (code "62") (name "SAWCORE") (class "Default")
      (node (ref "IC2") (pin "1") (pinfunction "OUT_1") (pintype "output"))
      (node (ref "R11") (pin "1") (pinfunction "1_1") (pintype "passive"))
      (node (ref "R12") (pin "1") (pinfunction "1_1") (pintype "passive"))
      (node (ref "R14") (pin "2") (pinfunction "2_2") (pintype "passive"))
    )
    (net (code "63") (name "SINE") (class "Default")
      (node (ref "IC6") (pin "7") (pinfunction "OUT_7") (pintype "output"))
      (node (ref "R46") (pin "1") (pinfunction "1_1") (pintype "passive"))
      (node (ref "SINE") (pin "TIP") (pinfunction "TIP_TIP") (pintype "passive"))
      (node (ref "SINE_MIX") (pin "P$3") (pinfunction "3_P$3") (pintype "passive"))
    )
    (net (code "64") (name "TRI") (class "Default")
      (node (ref "R33") (pin "1") (pinfunction "1_1") (pintype "passive"))
      (node (ref "R34") (pin "1") (pinfunction "1_1") (pintype "passive"))
      (node (ref "R35") (pin "2") (pinfunction "2_2") (pintype "passive"))
      (node (ref "TRI") (pin "TIP") (pinfunction "TIP_TIP") (pintype "passive"))
      (node (ref "TRI_MIX") (pin "P$3") (pinfunction "3_P$3") (pintype "passive"))
    )
    (net (code "65") (name "unconnected-(IC8-NC-Pad3)") (class "Default")
      (node (ref "IC8") (pin "3") (pinfunction "NC_3") (pintype "no_connect"))
    )
    (net (code "66") (name "unconnected-(MIX-SWITCH-PadNORM)") (class "Default")
      (node (ref "MIX") (pin "NORM") (pinfunction "SWITCH_NORM") (pintype "passive"))
    )
    (net (code "67") (name "unconnected-(PULSE-SWITCH-PadNORM)") (class "Default")
      (node (ref "PULSE") (pin "NORM") (pinfunction "SWITCH_NORM") (pintype "passive"))
    )
    (net (code "68") (name "unconnected-(PWM_IN-SWITCH-PadNORM)") (class "Default")
      (node (ref "PWM_IN") (pin "NORM") (pinfunction "SWITCH_NORM") (pintype "passive"))
    )
    (net (code "69") (name "unconnected-(SAW-SWITCH-PadNORM)") (class "Default")
      (node (ref "SAW") (pin "NORM") (pinfunction "SWITCH_NORM") (pintype "passive"))
    )
    (net (code "70") (name "unconnected-(SINE-SWITCH-PadNORM)") (class "Default")
      (node (ref "SINE") (pin "NORM") (pinfunction "SWITCH_NORM") (pintype "passive"))
    )
    (net (code "71") (name "unconnected-(SYNC-SWITCH-PadNORM)") (class "Default")
      (node (ref "SYNC") (pin "NORM") (pinfunction "SWITCH_NORM") (pintype "passive"))
    )
    (net (code "72") (name "unconnected-(TRI-SWITCH-PadNORM)") (class "Default")
      (node (ref "TRI") (pin "NORM") (pinfunction "SWITCH_NORM") (pintype "passive"))
    )
  )
)
